# matrix_segmen_shalat.net
KiCad netlist of a schematic drawn in EAGLE
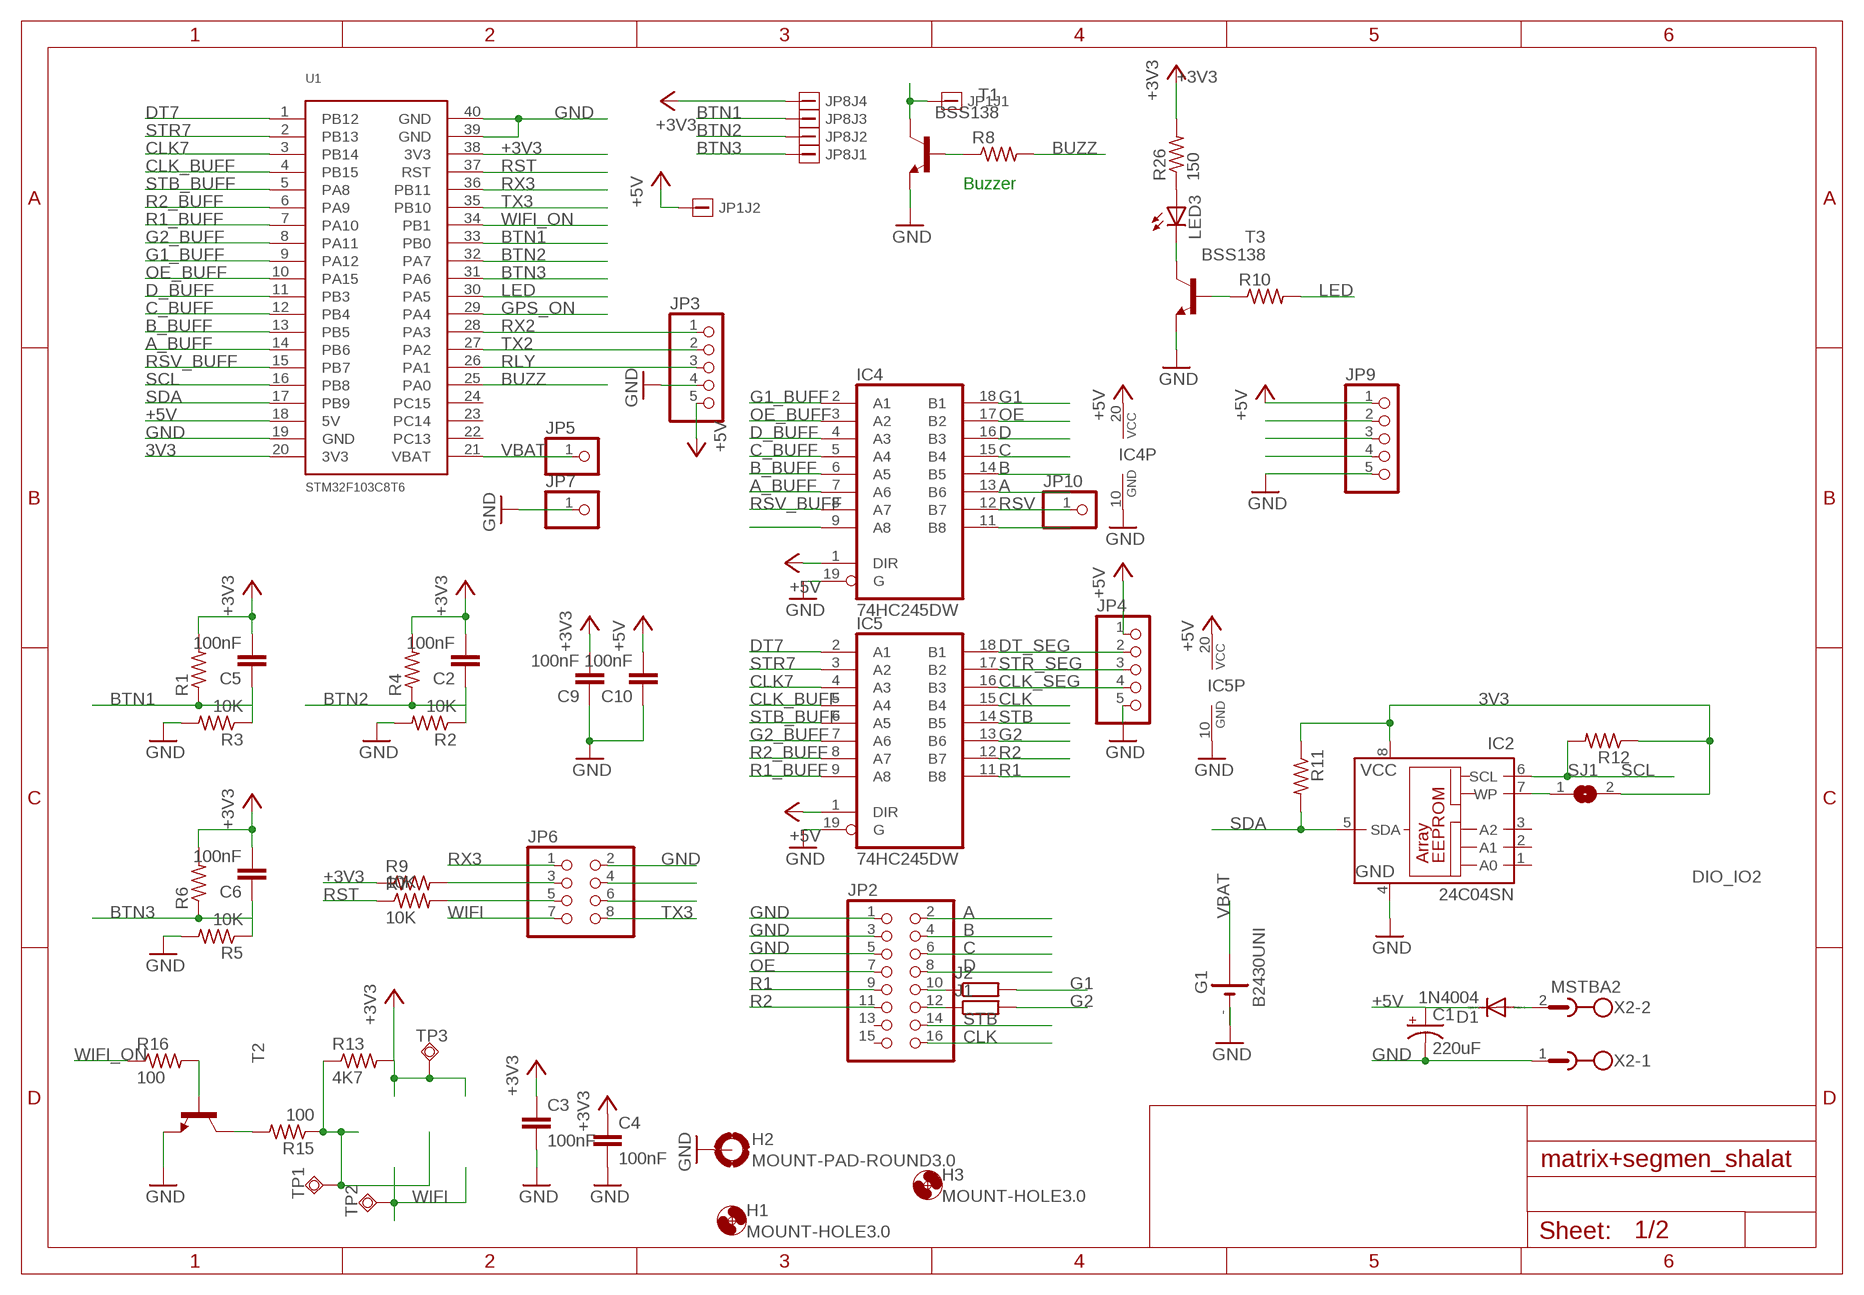
[diagram p0: schematic, sheet 1]
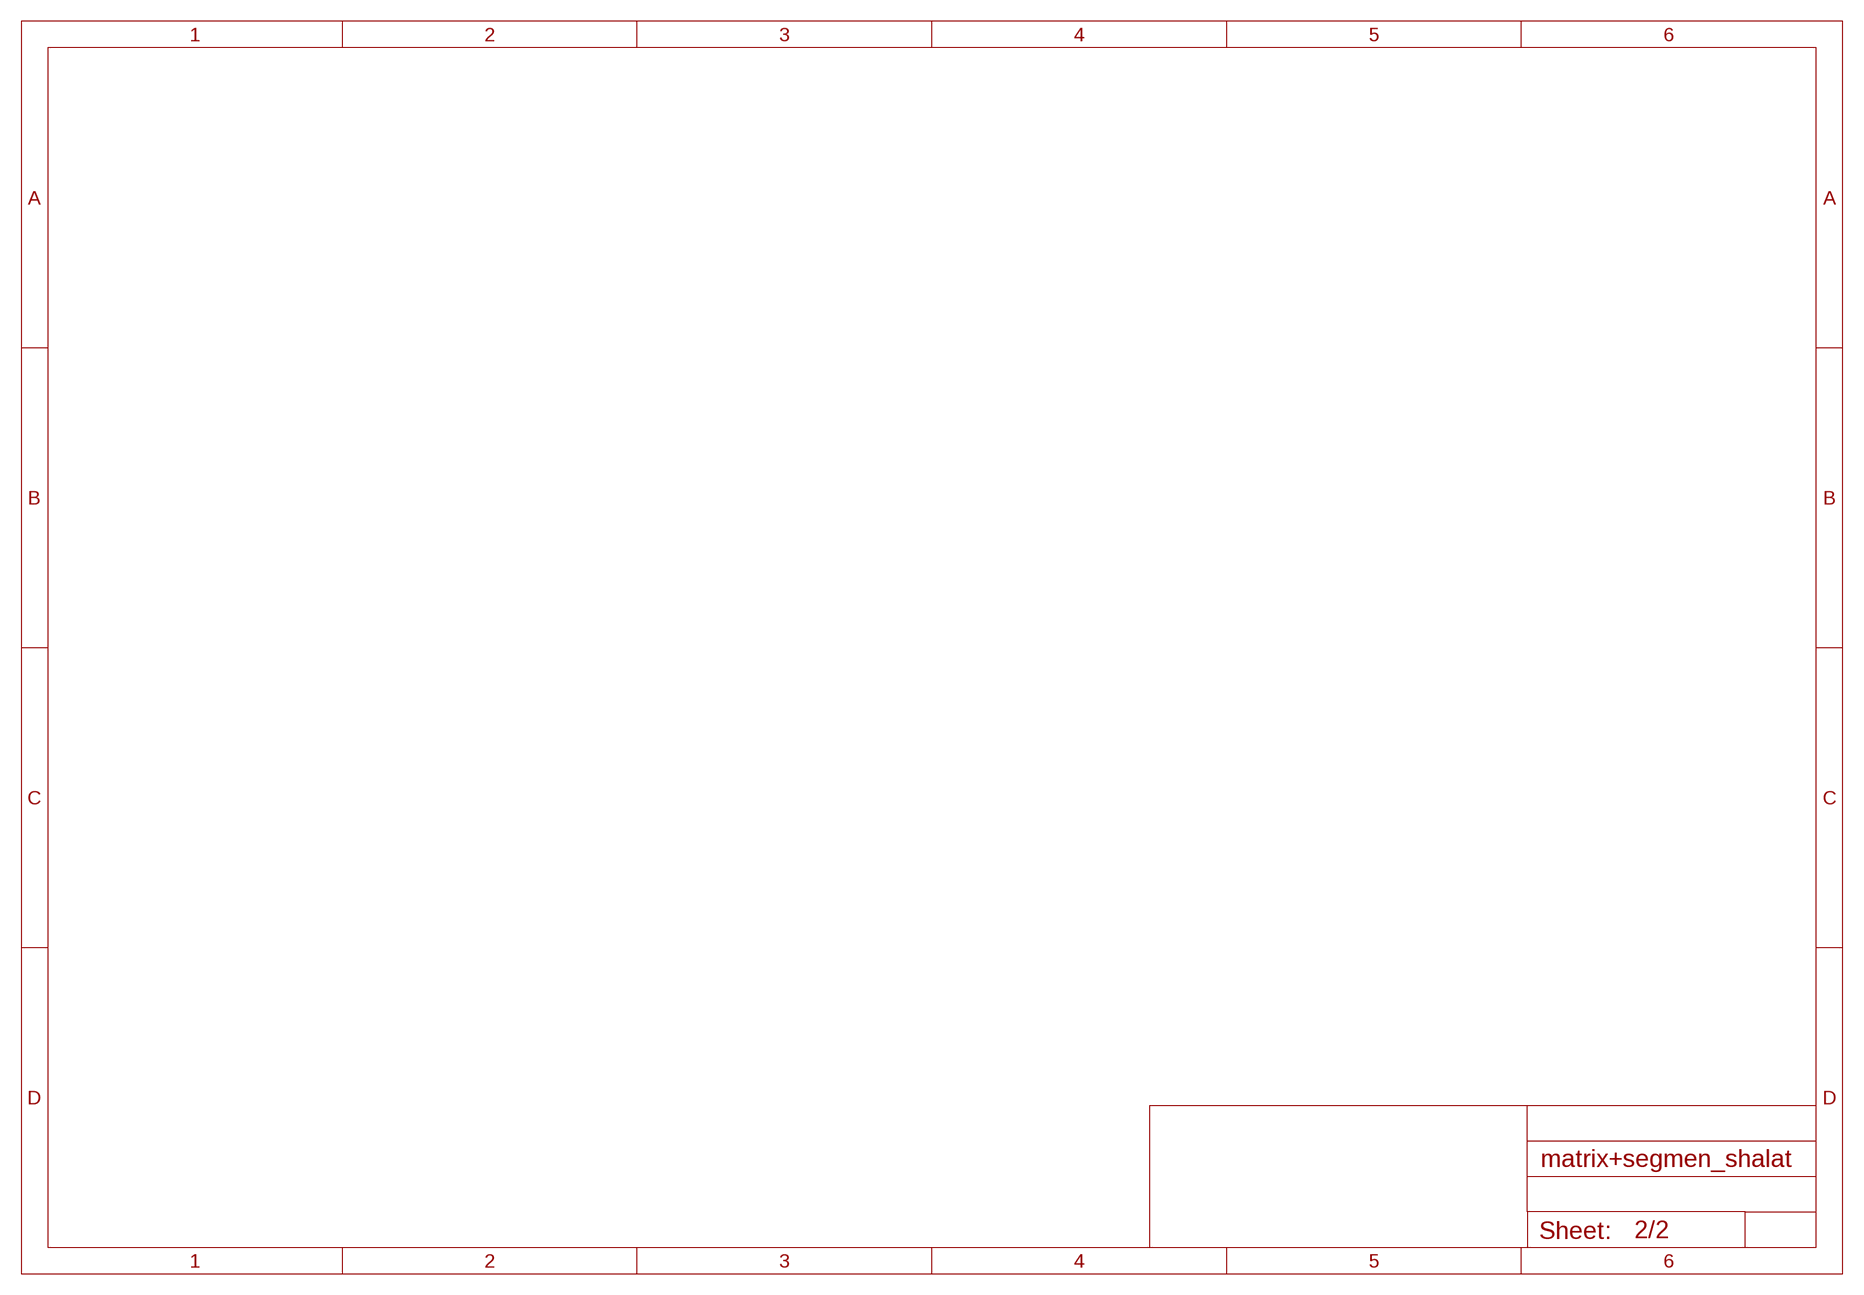
[diagram p1: schematic, sheet 2]

(export (version "E")
  (design (tool "Eeschema 10.0.6"))
  (components
    (comp (ref "C1")
      (value "220uF")
      (footprint "eagle-import:E3,5-8")
      (libsource (lib "eagle-import") (part "CPOL-USE3.5-8"))
    )
    (comp (ref "C2")
      (value "100nF")
      (footprint "eagle-import:C0805")
      (libsource (lib "eagle-import") (part "resistor_C-EUC0805"))
    )
    (comp (ref "C3")
      (value "100nF")
      (footprint "eagle-import:C0805")
      (libsource (lib "eagle-import") (part "C-EUC0805"))
    )
    (comp (ref "C4")
      (value "100nF")
      (footprint "eagle-import:C0805")
      (libsource (lib "eagle-import") (part "C-EUC0805"))
    )
    (comp (ref "C5")
      (value "100nF")
      (footprint "eagle-import:C0805")
      (libsource (lib "eagle-import") (part "resistor_C-EUC0805"))
    )
    (comp (ref "C6")
      (value "100nF")
      (footprint "eagle-import:C0805")
      (libsource (lib "eagle-import") (part "resistor_C-EUC0805"))
    )
    (comp (ref "C9")
      (value "100nF")
      (footprint "eagle-import:C0805")
      (libsource (lib "eagle-import") (part "resistor_C-EUC0805"))
    )
    (comp (ref "C10")
      (value "100nF")
      (footprint "eagle-import:C0805")
      (libsource (lib "eagle-import") (part "resistor_C-EUC0805"))
    )
    (comp (ref "D1")
      (value "1N4004")
      (footprint "eagle-import:DO41-10")
      (libsource (lib "eagle-import") (part "1N4004"))
    )
    (comp (ref "G1")
      (value "B2430UNI")
      (footprint "eagle-import:B2430UNI")
      (libsource (lib "eagle-import") (part "B2430UNI"))
    )
    (comp (ref "H1")
      (value "MOUNT-HOLE3.0")
      (footprint "eagle-import:3,0")
      (libsource (lib "eagle-import") (part "MOUNT-HOLE3.0"))
    )
    (comp (ref "H2")
      (value "MOUNT-PAD-ROUND3.0")
      (footprint "eagle-import:3,0-PAD")
      (libsource (lib "eagle-import") (part "MOUNT-PAD-ROUND3.0"))
    )
    (comp (ref "H3")
      (value "MOUNT-HOLE3.0")
      (footprint "eagle-import:3,0")
      (libsource (lib "eagle-import") (part "MOUNT-HOLE3.0"))
    )
    (comp (ref "IC2")
      (value "24C04SN")
      (footprint "eagle-import:SO-08")
      (fields (field (name "MPN") "M24C04-WMN6P"))
      (libsource (lib "eagle-import") (part "24CSN04"))
    )
    (comp (ref "IC4")
      (value "74HC245DW")
      (footprint "eagle-import:SO20W")
      (libsource (lib "eagle-import") (part "74245DWHC"))
    )
    (comp (ref "IC5")
      (value "74HC245DW")
      (footprint "eagle-import:SO20W")
      (libsource (lib "eagle-import") (part "74245DWHC"))
    )
    (comp (ref "J1")
      (value "R-EU_R0402")
      (footprint "eagle-import:R0402")
      (libsource (lib "eagle-import") (part "R-EU_R0402"))
    )
    (comp (ref "J2")
      (value "R-EU_R0402")
      (footprint "eagle-import:R0402")
      (libsource (lib "eagle-import") (part "R-EU_R0402"))
    )
    (comp (ref "JP1")
      (value "CON2-3.81")
      (footprint "eagle-import:CON2-3.81")
      (libsource (lib "eagle-import") (part "CON2-3.81"))
    )
    (comp (ref "JP2")
      (value "PINHD-2X8")
      (footprint "eagle-import:2X08")
      (libsource (lib "eagle-import") (part "PINHD-2X8"))
    )
    (comp (ref "JP3")
      (value "PINHD-1X5")
      (footprint "eagle-import:1X05")
      (libsource (lib "eagle-import") (part "PINHD-1X5"))
    )
    (comp (ref "JP4")
      (value "PINHD-1X5")
      (footprint "eagle-import:1X05")
      (libsource (lib "eagle-import") (part "PINHD-1X5"))
    )
    (comp (ref "JP5")
      (value "PINHD-1X1")
      (footprint "eagle-import:1X01")
      (libsource (lib "eagle-import") (part "PINHD-1X1"))
    )
    (comp (ref "JP6")
      (value "PINHD-2X4")
      (footprint "eagle-import:2X04")
      (libsource (lib "eagle-import") (part "PINHD-2X4"))
    )
    (comp (ref "JP7")
      (value "PINHD-1X1")
      (footprint "eagle-import:1X01")
      (libsource (lib "eagle-import") (part "PINHD-1X1"))
    )
    (comp (ref "JP8")
      (value "CON4-3.81")
      (footprint "eagle-import:CON4-3.81")
      (libsource (lib "eagle-import") (part "CON4-3.81"))
    )
    (comp (ref "JP9")
      (value "PINHD-1X5")
      (footprint "eagle-import:1X05")
      (libsource (lib "eagle-import") (part "PINHD-1X5"))
    )
    (comp (ref "JP10")
      (value "PINHD-1X1")
      (footprint "eagle-import:1X01")
      (libsource (lib "eagle-import") (part "PINHD-1X1"))
    )
    (comp (ref "LED3")
      (value "LED3MM")
      (footprint "eagle-import:LED3MM")
      (libsource (lib "eagle-import") (part "LED3MM"))
    )
    (comp (ref "R1")
      (value "R-US_0204/2V")
      (footprint "eagle-import:0204V")
      (libsource (lib "eagle-import") (part "rcl_334_R-US_0204/2V"))
    )
    (comp (ref "R2")
      (value "10K")
      (footprint "eagle-import:M0805")
      (libsource (lib "eagle-import") (part "R-US_M0805"))
    )
    (comp (ref "R3")
      (value "10K")
      (footprint "eagle-import:M0805")
      (libsource (lib "eagle-import") (part "R-US_M0805"))
    )
    (comp (ref "R4")
      (value "R-US_0204/2V")
      (footprint "eagle-import:0204V")
      (libsource (lib "eagle-import") (part "rcl_334_R-US_0204/2V"))
    )
    (comp (ref "R5")
      (value "10K")
      (footprint "eagle-import:M0805")
      (libsource (lib "eagle-import") (part "R-US_M0805"))
    )
    (comp (ref "R6")
      (value "R-US_0204/2V")
      (footprint "eagle-import:0204V")
      (libsource (lib "eagle-import") (part "rcl_334_R-US_0204/2V"))
    )
    (comp (ref "R7")
      (value "10K")
      (footprint "eagle-import:R0805")
      (libsource (lib "eagle-import") (part "R-US_R0805"))
    )
    (comp (ref "R8")
      (value "R-US_R0805")
      (footprint "eagle-import:R0805")
      (libsource (lib "eagle-import") (part "R-US_R0805"))
    )
    (comp (ref "R9")
      (value "10K")
      (footprint "eagle-import:R0805")
      (libsource (lib "eagle-import") (part "R-US_R0805"))
    )
    (comp (ref "R10")
      (value "R-US_R0805")
      (footprint "eagle-import:R0805")
      (libsource (lib "eagle-import") (part "R-US_R0805"))
    )
    (comp (ref "R11")
      (value "R-US_R0805")
      (footprint "eagle-import:R0805")
      (libsource (lib "eagle-import") (part "R-US_R0805"))
    )
    (comp (ref "R12")
      (value "R-US_R0805")
      (footprint "eagle-import:R0805")
      (libsource (lib "eagle-import") (part "R-US_R0805"))
    )
    (comp (ref "R13")
      (value "4K7")
      (footprint "eagle-import:R0805")
      (libsource (lib "eagle-import") (part "R-US_R0805"))
    )
    (comp (ref "R15")
      (value "100")
      (footprint "eagle-import:R0805")
      (libsource (lib "eagle-import") (part "R-US_R0805"))
    )
    (comp (ref "R16")
      (value "100")
      (footprint "eagle-import:R0805")
      (libsource (lib "eagle-import") (part "R-US_R0805"))
    )
    (comp (ref "R26")
      (value "150")
      (footprint "eagle-import:R0805")
      (libsource (lib "eagle-import") (part "R-US_R0805"))
    )
    (comp (ref "SJ1") (value "SJ") (footprint "eagle-import:SJ") (libsource (lib "eagle-import") (part "SJ")))
    (comp (ref "T1")
      (value "BSS138")
      (footprint "eagle-import:SOT23-BEC")
      (libsource (lib "eagle-import") (part "-NPN-SOT23-BECMMBT2222ALT1"))
    )
    (comp (ref "T2")
      (value "MMBT2222ALT1-NPN-SOT23-BEC")
      (footprint "eagle-import:SOT23-BEC")
      (libsource (lib "eagle-import") (part "-NPN-SOT23-BECMMBT2222ALT1"))
    )
    (comp (ref "T3")
      (value "BSS138")
      (footprint "eagle-import:SOT23-BEC")
      (libsource (lib "eagle-import") (part "-NPN-SOT23-BECMMBT2222ALT1"))
    )
    (comp (ref "TP1")
      (value "TPSQPAD1-13Y")
      (footprint "eagle-import:P1-13Y")
      (libsource (lib "eagle-import") (part "TPSQPAD1-13Y"))
    )
    (comp (ref "TP2")
      (value "TPSQPAD1-13Y")
      (footprint "eagle-import:P1-13Y")
      (libsource (lib "eagle-import") (part "TPSQPAD1-13Y"))
    )
    (comp (ref "TP3")
      (value "TPSQPAD1-13Y")
      (footprint "eagle-import:P1-13Y")
      (libsource (lib "eagle-import") (part "TPSQPAD1-13Y"))
    )
    (comp (ref "U1")
      (value "STM32F103C8T6")
      (footprint "eagle-import:STM32F103")
      (libsource (lib "eagle-import") (part "STM32F103C8T6"))
    )
    (comp (ref "X2")
      (value "MSTBA2")
      (footprint "eagle-import:MSTBA2")
      (fields (field (name "MF") "FARNELL") (field (name "MPN") "1757242"))
      (libsource (lib "eagle-import") (part "MSTBA2"))
    )
  )
  (nets
    (net (code "1") (name "+3V3") (class "Default")
      (node (ref "C2") (pin "2") (pinfunction "2_2") (pintype "passive"))
      (node (ref "C3") (pin "1") (pinfunction "1_1") (pintype "passive"))
      (node (ref "C4") (pin "1") (pinfunction "1_1") (pintype "passive"))
      (node (ref "C5") (pin "2") (pinfunction "2_2") (pintype "passive"))
      (node (ref "C6") (pin "2") (pinfunction "2_2") (pintype "passive"))
      (node (ref "C9") (pin "2") (pinfunction "2_2") (pintype "passive"))
      (node (ref "JP8") (pin "4") (pinfunction "1_4") (pintype "passive"))
      (node (ref "R1") (pin "2") (pinfunction "2_2") (pintype "passive"))
      (node (ref "R13") (pin "2") (pinfunction "2_2") (pintype "passive"))
      (node (ref "R26") (pin "2") (pinfunction "2_2") (pintype "passive"))
      (node (ref "R4") (pin "2") (pinfunction "2_2") (pintype "passive"))
      (node (ref "R6") (pin "2") (pinfunction "2_2") (pintype "passive"))
      (node (ref "R9") (pin "1") (pinfunction "1_1") (pintype "passive"))
      (node (ref "TP3") (pin "TP") (pinfunction "TP_TP") (pintype "input"))
      (node (ref "U1") (pin "38") (pinfunction "3V3_38") (pintype "bidirectional"))
    )
    (net (code "2") (name "+5V") (class "Default")
      (node (ref "C1") (pin "+") (pinfunction "+_+") (pintype "passive"))
      (node (ref "C10") (pin "2") (pinfunction "2_2") (pintype "passive"))
      (node (ref "D1") (pin "C") (pinfunction "C_C") (pintype "passive"))
      (node (ref "IC4") (pin "1") (pinfunction "DIR_1") (pintype "input"))
      (node (ref "IC4") (pin "20") (pinfunction "VCC_20") (pintype "power_in"))
      (node (ref "IC5") (pin "1") (pinfunction "DIR_1") (pintype "input"))
      (node (ref "IC5") (pin "20") (pinfunction "VCC_20") (pintype "power_in"))
      (node (ref "JP1") (pin "2") (pinfunction "1_2") (pintype "passive"))
      (node (ref "JP3") (pin "5") (pinfunction "5_5") (pintype "passive"))
      (node (ref "JP4") (pin "1") (pinfunction "1_1") (pintype "passive"))
      (node (ref "JP9") (pin "1") (pinfunction "1_1") (pintype "passive"))
      (node (ref "U1") (pin "18") (pinfunction "5V_18") (pintype "bidirectional"))
    )
    (net (code "3") (name "3V3") (class "Default")
      (node (ref "IC2") (pin "8") (pinfunction "VCC_8") (pintype "power_in"))
      (node (ref "R11") (pin "1") (pinfunction "1_1") (pintype "passive"))
      (node (ref "R12") (pin "1") (pinfunction "1_1") (pintype "passive"))
      (node (ref "SJ1") (pin "2") (pinfunction "2_2") (pintype "passive"))
      (node (ref "U1") (pin "20") (pinfunction "3V3_20") (pintype "bidirectional"))
    )
    (net (code "4") (name "A") (class "Default")
      (node (ref "IC4") (pin "13") (pinfunction "B6_13") (pintype "bidirectional"))
      (node (ref "JP2") (pin "2") (pinfunction "2_2") (pintype "passive"))
    )
    (net (code "5") (name "A_BUFF") (class "Default")
      (node (ref "IC4") (pin "7") (pinfunction "A6_7") (pintype "bidirectional"))
      (node (ref "U1") (pin "14") (pinfunction "PB6_14") (pintype "bidirectional"))
    )
    (net (code "6") (name "B") (class "Default")
      (node (ref "IC4") (pin "14") (pinfunction "B5_14") (pintype "bidirectional"))
      (node (ref "JP2") (pin "4") (pinfunction "4_4") (pintype "passive"))
    )
    (net (code "7") (name "BTN1") (class "Default")
      (node (ref "C5") (pin "1") (pinfunction "1_1") (pintype "passive"))
      (node (ref "JP8") (pin "3") (pinfunction "1_3") (pintype "passive"))
      (node (ref "R1") (pin "1") (pinfunction "1_1") (pintype "passive"))
      (node (ref "R3") (pin "1") (pinfunction "1_1") (pintype "passive"))
      (node (ref "U1") (pin "33") (pinfunction "PB0_33") (pintype "bidirectional"))
    )
    (net (code "8") (name "BTN2") (class "Default")
      (node (ref "C2") (pin "1") (pinfunction "1_1") (pintype "passive"))
      (node (ref "JP8") (pin "2") (pinfunction "1_2") (pintype "passive"))
      (node (ref "R2") (pin "1") (pinfunction "1_1") (pintype "passive"))
      (node (ref "R4") (pin "1") (pinfunction "1_1") (pintype "passive"))
      (node (ref "U1") (pin "32") (pinfunction "PA7_32") (pintype "bidirectional"))
    )
    (net (code "9") (name "BTN3") (class "Default")
      (node (ref "C6") (pin "1") (pinfunction "1_1") (pintype "passive"))
      (node (ref "JP8") (pin "1") (pinfunction "1_1") (pintype "passive"))
      (node (ref "R5") (pin "1") (pinfunction "1_1") (pintype "passive"))
      (node (ref "R6") (pin "1") (pinfunction "1_1") (pintype "passive"))
      (node (ref "U1") (pin "31") (pinfunction "PA6_31") (pintype "bidirectional"))
    )
    (net (code "10") (name "BUZZ") (class "Default")
      (node (ref "R8") (pin "2") (pinfunction "2_2") (pintype "passive"))
      (node (ref "U1") (pin "25") (pinfunction "PA0_25") (pintype "bidirectional"))
    )
    (net (code "11") (name "B_BUFF") (class "Default")
      (node (ref "IC4") (pin "6") (pinfunction "A5_6") (pintype "bidirectional"))
      (node (ref "U1") (pin "13") (pinfunction "PB5_13") (pintype "bidirectional"))
    )
    (net (code "12") (name "C") (class "Default")
      (node (ref "IC4") (pin "15") (pinfunction "B4_15") (pintype "bidirectional"))
      (node (ref "JP2") (pin "6") (pinfunction "6_6") (pintype "passive"))
    )
    (net (code "13") (name "CLK") (class "Default")
      (node (ref "IC5") (pin "15") (pinfunction "B4_15") (pintype "bidirectional"))
      (node (ref "JP2") (pin "16") (pinfunction "16_16") (pintype "passive"))
    )
    (net (code "14") (name "CLK7") (class "Default")
      (node (ref "IC5") (pin "4") (pinfunction "A3_4") (pintype "bidirectional"))
      (node (ref "U1") (pin "3") (pinfunction "PB14_3") (pintype "bidirectional"))
    )
    (net (code "15") (name "CLK_BUFF") (class "Default")
      (node (ref "IC5") (pin "5") (pinfunction "A4_5") (pintype "bidirectional"))
      (node (ref "U1") (pin "4") (pinfunction "PB15_4") (pintype "bidirectional"))
    )
    (net (code "16") (name "CLK_SEG") (class "Default")
      (node (ref "IC5") (pin "16") (pinfunction "B3_16") (pintype "bidirectional"))
      (node (ref "JP4") (pin "4") (pinfunction "4_4") (pintype "passive"))
    )
    (net (code "17") (name "C_BUFF") (class "Default")
      (node (ref "IC4") (pin "5") (pinfunction "A4_5") (pintype "bidirectional"))
      (node (ref "U1") (pin "12") (pinfunction "PB4_12") (pintype "bidirectional"))
    )
    (net (code "18") (name "D") (class "Default")
      (node (ref "IC4") (pin "16") (pinfunction "B3_16") (pintype "bidirectional"))
      (node (ref "JP2") (pin "8") (pinfunction "8_8") (pintype "passive"))
    )
    (net (code "20") (name "DT7") (class "Default")
      (node (ref "IC5") (pin "2") (pinfunction "A1_2") (pintype "bidirectional"))
      (node (ref "U1") (pin "1") (pinfunction "PB12_1") (pintype "bidirectional"))
    )
    (net (code "21") (name "DT_SEG") (class "Default")
      (node (ref "IC5") (pin "18") (pinfunction "B1_18") (pintype "bidirectional"))
      (node (ref "JP4") (pin "2") (pinfunction "2_2") (pintype "passive"))
    )
    (net (code "22") (name "D_BUFF") (class "Default")
      (node (ref "IC4") (pin "4") (pinfunction "A3_4") (pintype "bidirectional"))
      (node (ref "U1") (pin "11") (pinfunction "PB3_11") (pintype "bidirectional"))
    )
    (net (code "23") (name "G1") (class "Default")
      (node (ref "IC4") (pin "18") (pinfunction "B1_18") (pintype "bidirectional"))
      (node (ref "J2") (pin "2") (pinfunction "2_2") (pintype "passive"))
    )
    (net (code "24") (name "G1_BUFF") (class "Default")
      (node (ref "IC4") (pin "2") (pinfunction "A1_2") (pintype "bidirectional"))
      (node (ref "U1") (pin "9") (pinfunction "PA12_9") (pintype "bidirectional"))
    )
    (net (code "25") (name "G2") (class "Default")
      (node (ref "IC5") (pin "13") (pinfunction "B6_13") (pintype "bidirectional"))
      (node (ref "J1") (pin "2") (pinfunction "2_2") (pintype "passive"))
    )
    (net (code "26") (name "G2_BUFF") (class "Default")
      (node (ref "IC5") (pin "7") (pinfunction "A6_7") (pintype "bidirectional"))
      (node (ref "U1") (pin "8") (pinfunction "PA11_8") (pintype "bidirectional"))
    )
    (net (code "27") (name "GND") (class "Default")
      (node (ref "C1") (pin "-") (pinfunction "-_-") (pintype "passive"))
      (node (ref "C10") (pin "1") (pinfunction "1_1") (pintype "passive"))
      (node (ref "C3") (pin "2") (pinfunction "2_2") (pintype "passive"))
      (node (ref "C4") (pin "2") (pinfunction "2_2") (pintype "passive"))
      (node (ref "C9") (pin "1") (pinfunction "1_1") (pintype "passive"))
      (node (ref "G1") (pin "-") (pinfunction "-_-") (pintype "passive"))
      (node (ref "G1") (pin "-@1") (pinfunction "-_-@1") (pintype "passive"))
      (node (ref "H2") (pin "B3,0") (pinfunction "MOUNT_B3,0") (pintype "passive"))
      (node (ref "IC2") (pin "4") (pinfunction "GND_4") (pintype "power_in"))
      (node (ref "IC4") (pin "10") (pinfunction "GND_10") (pintype "power_in"))
      (node (ref "IC4") (pin "19") (pinfunction "G_19") (pintype "input"))
      (node (ref "IC5") (pin "10") (pinfunction "GND_10") (pintype "power_in"))
      (node (ref "IC5") (pin "19") (pinfunction "G_19") (pintype "input"))
      (node (ref "JP2") (pin "1") (pinfunction "1_1") (pintype "passive"))
      (node (ref "JP2") (pin "3") (pinfunction "3_3") (pintype "passive"))
      (node (ref "JP2") (pin "5") (pinfunction "5_5") (pintype "passive"))
      (node (ref "JP3") (pin "4") (pinfunction "4_4") (pintype "passive"))
      (node (ref "JP4") (pin "5") (pinfunction "5_5") (pintype "passive"))
      (node (ref "JP6") (pin "2") (pinfunction "2_2") (pintype "passive"))
      (node (ref "JP7") (pin "1") (pinfunction "1_1") (pintype "passive"))
      (node (ref "JP9") (pin "5") (pinfunction "5_5") (pintype "passive"))
      (node (ref "R2") (pin "2") (pinfunction "2_2") (pintype "passive"))
      (node (ref "R3") (pin "2") (pinfunction "2_2") (pintype "passive"))
      (node (ref "R5") (pin "2") (pinfunction "2_2") (pintype "passive"))
      (node (ref "T1") (pin "E") (pinfunction "E_E") (pintype "passive"))
      (node (ref "T2") (pin "E") (pinfunction "E_E") (pintype "passive"))
      (node (ref "T3") (pin "E") (pinfunction "E_E") (pintype "passive"))
      (node (ref "U1") (pin "19") (pinfunction "GND_19") (pintype "bidirectional"))
      (node (ref "U1") (pin "39") (pinfunction "GND_39") (pintype "bidirectional"))
      (node (ref "U1") (pin "40") (pinfunction "GND_40") (pintype "bidirectional"))
      (node (ref "X2") (pin "1") (pinfunction "1_1") (pintype "passive"))
    )
    (net (code "28") (name "GPS_ON") (class "Default")
      (node (ref "U1") (pin "29") (pinfunction "PA4_29") (pintype "bidirectional"))
    )
    (net (code "29") (name "LED") (class "Default")
      (node (ref "R10") (pin "2") (pinfunction "2_2") (pintype "passive"))
      (node (ref "U1") (pin "30") (pinfunction "PA5_30") (pintype "bidirectional"))
    )
    (net (code "30") (name "Net-(IC2-WP)") (class "Default")
      (node (ref "IC2") (pin "7") (pinfunction "WP_7") (pintype "input"))
      (node (ref "SJ1") (pin "1") (pinfunction "1_1") (pintype "passive"))
    )
    (net (code "31") (name "Net-(J1-Pad1)") (class "Default")
      (node (ref "J1") (pin "1") (pinfunction "1_1") (pintype "passive"))
      (node (ref "JP2") (pin "12") (pinfunction "12_12") (pintype "passive"))
    )
    (net (code "32") (name "Net-(J2-Pad1)") (class "Default")
      (node (ref "J2") (pin "1") (pinfunction "1_1") (pintype "passive"))
      (node (ref "JP2") (pin "10") (pinfunction "10_10") (pintype "passive"))
    )
    (net (code "33") (name "Net-(JP1-Pad1)") (class "Default")
      (node (ref "JP1") (pin "1") (pinfunction "1_1") (pintype "passive"))
      (node (ref "T1") (pin "C") (pinfunction "C_C") (pintype "passive"))
    )
    (net (code "34") (name "Net-(JP6-Pad3)") (class "Default")
      (node (ref "JP6") (pin "3") (pinfunction "3_3") (pintype "passive"))
      (node (ref "R9") (pin "2") (pinfunction "2_2") (pintype "passive"))
    )
    (net (code "35") (name "Net-(JP6-Pad5)") (class "Default")
      (node (ref "JP6") (pin "5") (pinfunction "5_5") (pintype "passive"))
      (node (ref "R7") (pin "2") (pinfunction "2_2") (pintype "passive"))
    )
    (net (code "36") (name "Net-(LED3-C)") (class "Default")
      (node (ref "LED3") (pin "K") (pinfunction "C_K") (pintype "passive"))
      (node (ref "T3") (pin "C") (pinfunction "C_C") (pintype "passive"))
    )
    (net (code "37") (name "Net-(LED3-PadA)") (class "Default")
      (node (ref "LED3") (pin "A") (pinfunction "A_A") (pintype "passive"))
      (node (ref "R26") (pin "1") (pinfunction "1_1") (pintype "passive"))
    )
    (net (code "38") (name "Net-(R8-Pad1)") (class "Default")
      (node (ref "R8") (pin "1") (pinfunction "1_1") (pintype "passive"))
      (node (ref "T1") (pin "B") (pinfunction "B_B") (pintype "passive"))
    )
    (net (code "39") (name "Net-(R10-Pad1)") (class "Default")
      (node (ref "R10") (pin "1") (pinfunction "1_1") (pintype "passive"))
      (node (ref "T3") (pin "B") (pinfunction "B_B") (pintype "passive"))
    )
    (net (code "40") (name "Net-(R13-Pad1)") (class "Default")
      (node (ref "R13") (pin "1") (pinfunction "1_1") (pintype "passive"))
      (node (ref "R15") (pin "1") (pinfunction "1_1") (pintype "passive"))
      (node (ref "TP1") (pin "TP") (pinfunction "TP_TP") (pintype "input"))
    )
    (net (code "41") (name "Net-(R15-Pad2)") (class "Default")
      (node (ref "R15") (pin "2") (pinfunction "2_2") (pintype "passive"))
      (node (ref "T2") (pin "C") (pinfunction "C_C") (pintype "passive"))
    )
    (net (code "42") (name "Net-(R16-Pad2)") (class "Default")
      (node (ref "R16") (pin "2") (pinfunction "2_2") (pintype "passive"))
      (node (ref "T2") (pin "B") (pinfunction "B_B") (pintype "passive"))
    )
    (net (code "43") (name "Net-(X2B-1)") (class "Default")
      (node (ref "D1") (pin "A") (pinfunction "A_A") (pintype "passive"))
      (node (ref "X2") (pin "2") (pinfunction "1_2") (pintype "passive"))
    )
    (net (code "44") (name "OE") (class "Default")
      (node (ref "IC4") (pin "17") (pinfunction "B2_17") (pintype "bidirectional"))
      (node (ref "JP2") (pin "7") (pinfunction "7_7") (pintype "passive"))
    )
    (net (code "45") (name "OE_BUFF") (class "Default")
      (node (ref "IC4") (pin "3") (pinfunction "A2_3") (pintype "bidirectional"))
      (node (ref "U1") (pin "10") (pinfunction "PA15_10") (pintype "bidirectional"))
    )
    (net (code "46") (name "R1") (class "Default")
      (node (ref "IC5") (pin "11") (pinfunction "B8_11") (pintype "bidirectional"))
      (node (ref "JP2") (pin "9") (pinfunction "9_9") (pintype "passive"))
    )
    (net (code "47") (name "R1_BUFF") (class "Default")
      (node (ref "IC5") (pin "9") (pinfunction "A8_9") (pintype "bidirectional"))
      (node (ref "U1") (pin "7") (pinfunction "PA10_7") (pintype "bidirectional"))
    )
    (net (code "48") (name "R2") (class "Default")
      (node (ref "IC5") (pin "12") (pinfunction "B7_12") (pintype "bidirectional"))
      (node (ref "JP2") (pin "11") (pinfunction "11_11") (pintype "passive"))
    )
    (net (code "49") (name "R2_BUFF") (class "Default")
      (node (ref "IC5") (pin "8") (pinfunction "A7_8") (pintype "bidirectional"))
      (node (ref "U1") (pin "6") (pinfunction "PA9_6") (pintype "bidirectional"))
    )
    (net (code "50") (name "RLY") (class "Default")
      (node (ref "JP3") (pin "3") (pinfunction "3_3") (pintype "passive"))
      (node (ref "U1") (pin "26") (pinfunction "PA1_26") (pintype "bidirectional"))
    )
    (net (code "51") (name "RST") (class "Default")
      (node (ref "R7") (pin "1") (pinfunction "1_1") (pintype "passive"))
      (node (ref "U1") (pin "37") (pinfunction "RST_37") (pintype "bidirectional"))
    )
    (net (code "52") (name "RSV") (class "Default")
      (node (ref "IC4") (pin "12") (pinfunction "B7_12") (pintype "bidirectional"))
      (node (ref "JP10") (pin "1") (pinfunction "1_1") (pintype "passive"))
    )
    (net (code "53") (name "RSV_BUFF") (class "Default")
      (node (ref "IC4") (pin "8") (pinfunction "A7_8") (pintype "bidirectional"))
      (node (ref "U1") (pin "15") (pinfunction "PB7_15") (pintype "bidirectional"))
    )
    (net (code "54") (name "RX2") (class "Default")
      (node (ref "JP3") (pin "1") (pinfunction "1_1") (pintype "passive"))
      (node (ref "U1") (pin "28") (pinfunction "PA3_28") (pintype "bidirectional"))
    )
    (net (code "55") (name "RX3") (class "Default")
      (node (ref "JP6") (pin "1") (pinfunction "1_1") (pintype "passive"))
      (node (ref "U1") (pin "36") (pinfunction "PB11_36") (pintype "bidirectional"))
    )
    (net (code "56") (name "SCL") (class "Default")
      (node (ref "IC2") (pin "6") (pinfunction "SCL_6") (pintype "input"))
      (node (ref "R12") (pin "2") (pinfunction "2_2") (pintype "passive"))
      (node (ref "U1") (pin "16") (pinfunction "PB8_16") (pintype "bidirectional"))
    )
    (net (code "57") (name "SDA") (class "Default")
      (node (ref "IC2") (pin "5") (pinfunction "SDA_5") (pintype "bidirectional"))
      (node (ref "R11") (pin "2") (pinfunction "2_2") (pintype "passive"))
      (node (ref "U1") (pin "17") (pinfunction "PB9_17") (pintype "bidirectional"))
    )
    (net (code "58") (name "STB") (class "Default")
      (node (ref "IC5") (pin "14") (pinfunction "B5_14") (pintype "bidirectional"))
      (node (ref "JP2") (pin "14") (pinfunction "14_14") (pintype "passive"))
    )
    (net (code "59") (name "STB_BUFF") (class "Default")
      (node (ref "IC5") (pin "6") (pinfunction "A5_6") (pintype "bidirectional"))
      (node (ref "U1") (pin "5") (pinfunction "PA8_5") (pintype "bidirectional"))
    )
    (net (code "60") (name "STR7") (class "Default")
      (node (ref "IC5") (pin "3") (pinfunction "A2_3") (pintype "bidirectional"))
      (node (ref "U1") (pin "2") (pinfunction "PB13_2") (pintype "bidirectional"))
    )
    (net (code "61") (name "STR_SEG") (class "Default")
      (node (ref "IC5") (pin "17") (pinfunction "B2_17") (pintype "bidirectional"))
      (node (ref "JP4") (pin "3") (pinfunction "3_3") (pintype "passive"))
    )
    (net (code "62") (name "TX2") (class "Default")
      (node (ref "JP3") (pin "2") (pinfunction "2_2") (pintype "passive"))
      (node (ref "U1") (pin "27") (pinfunction "PA2_27") (pintype "bidirectional"))
    )
    (net (code "63") (name "TX3") (class "Default")
      (node (ref "JP6") (pin "8") (pinfunction "8_8") (pintype "passive"))
      (node (ref "U1") (pin "35") (pinfunction "PB10_35") (pintype "bidirectional"))
    )
    (net (code "64") (name "VBAT") (class "Default")
      (node (ref "G1") (pin "+@4") (pinfunction "+_+@4") (pintype "passive"))
      (node (ref "JP5") (pin "1") (pinfunction "1_1") (pintype "passive"))
      (node (ref "U1") (pin "21") (pinfunction "VBAT_21") (pintype "bidirectional"))
    )
    (net (code "65") (name "WIFI") (class "Default")
      (node (ref "JP6") (pin "7") (pinfunction "7_7") (pintype "passive"))
      (node (ref "TP2") (pin "TP") (pinfunction "TP_TP") (pintype "input"))
    )
    (net (code "66") (name "WIFI_ON") (class "Default")
      (node (ref "R16") (pin "1") (pinfunction "1_1") (pintype "passive"))
      (node (ref "U1") (pin "34") (pinfunction "PB1_34") (pintype "bidirectional"))
    )
    (net (code "67") (name "unconnected-(IC2-A0-Pad1)") (class "Default")
      (node (ref "IC2") (pin "1") (pinfunction "A0_1") (pintype "input"))
    )
    (net (code "68") (name "unconnected-(IC2-A1-Pad2)") (class "Default")
      (node (ref "IC2") (pin "2") (pinfunction "A1_2") (pintype "input"))
    )
    (net (code "69") (name "unconnected-(IC2-A2-Pad3)") (class "Default")
      (node (ref "IC2") (pin "3") (pinfunction "A2_3") (pintype "input"))
    )
    (net (code "70") (name "unconnected-(IC4A-A8-Pad9)") (class "Default")
      (node (ref "IC4") (pin "9") (pinfunction "A8_9") (pintype "bidirectional"))
    )
    (net (code "71") (name "unconnected-(IC4A-B8-Pad11)") (class "Default")
      (node (ref "IC4") (pin "11") (pinfunction "B8_11") (pintype "bidirectional"))
    )
    (net (code "72") (name "unconnected-(JP2-Pad13)") (class "Default")
      (node (ref "JP2") (pin "13") (pinfunction "13_13") (pintype "passive"))
    )
    (net (code "73") (name "unconnected-(JP2-Pad15)") (class "Default")
      (node (ref "JP2") (pin "15") (pinfunction "15_15") (pintype "passive"))
    )
    (net (code "74") (name "unconnected-(JP6-Pad4)") (class "Default")
      (node (ref "JP6") (pin "4") (pinfunction "4_4") (pintype "passive"))
    )
    (net (code "75") (name "unconnected-(JP6-Pad6)") (class "Default")
      (node (ref "JP6") (pin "6") (pinfunction "6_6") (pintype "passive"))
    )
    (net (code "76") (name "unconnected-(JP9-Pad2)") (class "Default")
      (node (ref "JP9") (pin "2") (pinfunction "2_2") (pintype "passive"))
    )
    (net (code "77") (name "unconnected-(JP9-Pad3)") (class "Default")
      (node (ref "JP9") (pin "3") (pinfunction "3_3") (pintype "passive"))
    )
    (net (code "78") (name "unconnected-(JP9-Pad4)") (class "Default")
      (node (ref "JP9") (pin "4") (pinfunction "4_4") (pintype "passive"))
    )
    (net (code "79") (name "unconnected-(U1-PC13-Pad22)") (class "Default")
      (node (ref "U1") (pin "22") (pinfunction "PC13_22") (pintype "bidirectional"))
    )
    (net (code "80") (name "unconnected-(U1-PC14-Pad23)") (class "Default")
      (node (ref "U1") (pin "23") (pinfunction "PC14_23") (pintype "bidirectional"))
    )
    (net (code "81") (name "unconnected-(U1-PC15-Pad24)") (class "Default")
      (node (ref "U1") (pin "24") (pinfunction "PC15_24") (pintype "bidirectional"))
    )
  )
)
